# QCopterFC_POWER_Sch.net
KiCad netlist of a schematic drawn in Altium Designer
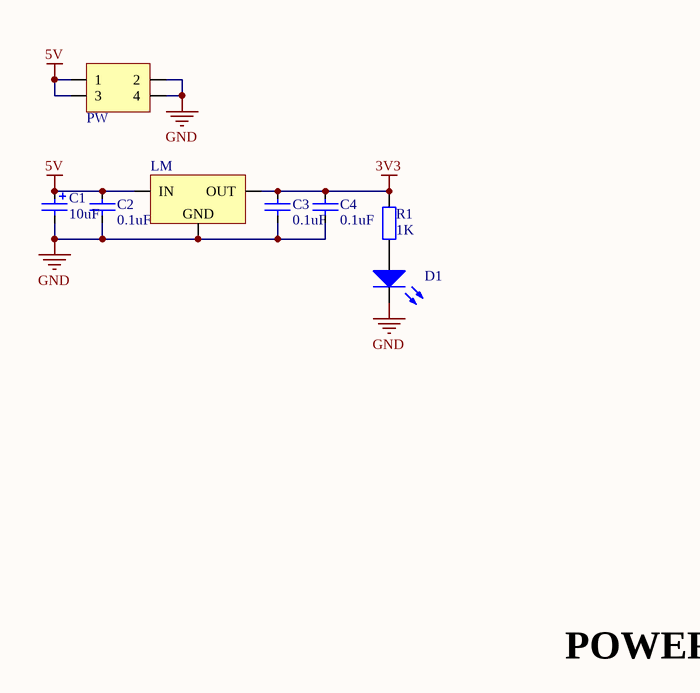
[diagram p0: QCopterFC_POWER_Sch.SchDoc]

(export (version "E")
  (design (tool "Eeschema 10.0.6"))
  (components
    (comp (ref "C1")
      (value "10uF")
      (footprint "PCB_Passive:CAP_TAN_B1210")
      (description "Capacitor")
      (fields (field (name "Comment") "Cap_Tan_1210"))
      (libsource (lib "SCH_Passive") (part "Cap_Tan_1210"))
    )
    (comp (ref "C2")
      (value "0.1uF")
      (footprint "PCB_Passive:CAP_0603")
      (description "Capacitor")
      (fields (field (name "Comment") "Cap_0603"))
      (libsource (lib "SCH_Passive") (part "Cap_0603"))
    )
    (comp (ref "C3")
      (value "0.1uF")
      (footprint "PCB_Passive:CAP_0603")
      (description "Capacitor")
      (fields (field (name "Comment") "Cap_0603"))
      (libsource (lib "SCH_Passive") (part "Cap_0603"))
    )
    (comp (ref "C4")
      (value "0.1uF")
      (footprint "PCB_Passive:CAP_0603")
      (description "Capacitor")
      (fields (field (name "Comment") "Cap_0603"))
      (libsource (lib "SCH_Passive") (part "Cap_0603"))
    )
    (comp (ref "D1")
      (value "LED_0603_BLUE")
      (footprint "PCB_Active:LED_0603_BLUE")
      (description "LED")
      (libsource (lib "SCH_Active") (part "LED_0603_BLUE"))
    )
    (comp (ref "LM")
      (value "LM1117")
      (footprint "PCB_IC:SOT223")
      (description "Power")
      (libsource (lib "SCH_IC") (part "LM1117"))
    )
    (comp (ref "PW")
      (value "HDR2X2_90_2.54")
      (footprint "PCB_Connector:HDR2X2_90_2.54")
      (description "Header")
      (libsource (lib "SCH_Connector") (part "HDR2X2_90_2.54"))
    )
    (comp (ref "R1")
      (value "1K")
      (footprint "PCB_Passive:RES_0603")
      (description "Resistor")
      (fields (field (name "Comment") "Res_0603"))
      (libsource (lib "SCH_Passive") (part "Res_0603"))
    )
  )
  (nets
    (net (code "1") (name "3V3") (class "Default")
      (node (ref "C3") (pin "2") (pinfunction "2_2") (pintype "passive"))
      (node (ref "C4") (pin "2") (pinfunction "2_2") (pintype "passive"))
      (node (ref "LM") (pin "2") (pinfunction "OUT_2") (pintype "power_in"))
      (node (ref "R1") (pin "2") (pinfunction "2_2") (pintype "passive"))
    )
    (net (code "2") (name "5V") (class "Default")
      (node (ref "C1") (pin "1") (pinfunction "1_1") (pintype "passive"))
      (node (ref "C2") (pin "2") (pinfunction "2_2") (pintype "passive"))
      (node (ref "LM") (pin "3") (pinfunction "IN_3") (pintype "power_in"))
      (node (ref "PW") (pin "1") (pinfunction "1_1") (pintype "passive"))
      (node (ref "PW") (pin "3") (pinfunction "3_3") (pintype "passive"))
    )
    (net (code "3") (name "GND") (class "Default")
      (node (ref "C1") (pin "2") (pinfunction "2_2") (pintype "passive"))
      (node (ref "C2") (pin "1") (pinfunction "1_1") (pintype "passive"))
      (node (ref "C3") (pin "1") (pinfunction "1_1") (pintype "passive"))
      (node (ref "C4") (pin "1") (pinfunction "1_1") (pintype "passive"))
      (node (ref "D1") (pin "2") (pinfunction "K_2") (pintype "passive"))
      (node (ref "LM") (pin "1") (pinfunction "GND_1") (pintype "power_in"))
      (node (ref "PW") (pin "2") (pinfunction "2_2") (pintype "passive"))
      (node (ref "PW") (pin "4") (pinfunction "4_4") (pintype "passive"))
    )
    (net (code "4") (name "Net-(D1-A)") (class "Default")
      (node (ref "D1") (pin "1") (pinfunction "A_1") (pintype "passive"))
      (node (ref "R1") (pin "1") (pinfunction "1_1") (pintype "passive"))
    )
  )
)
